# ForceReset.net
KiCad netlist of a schematic drawn in EAGLE
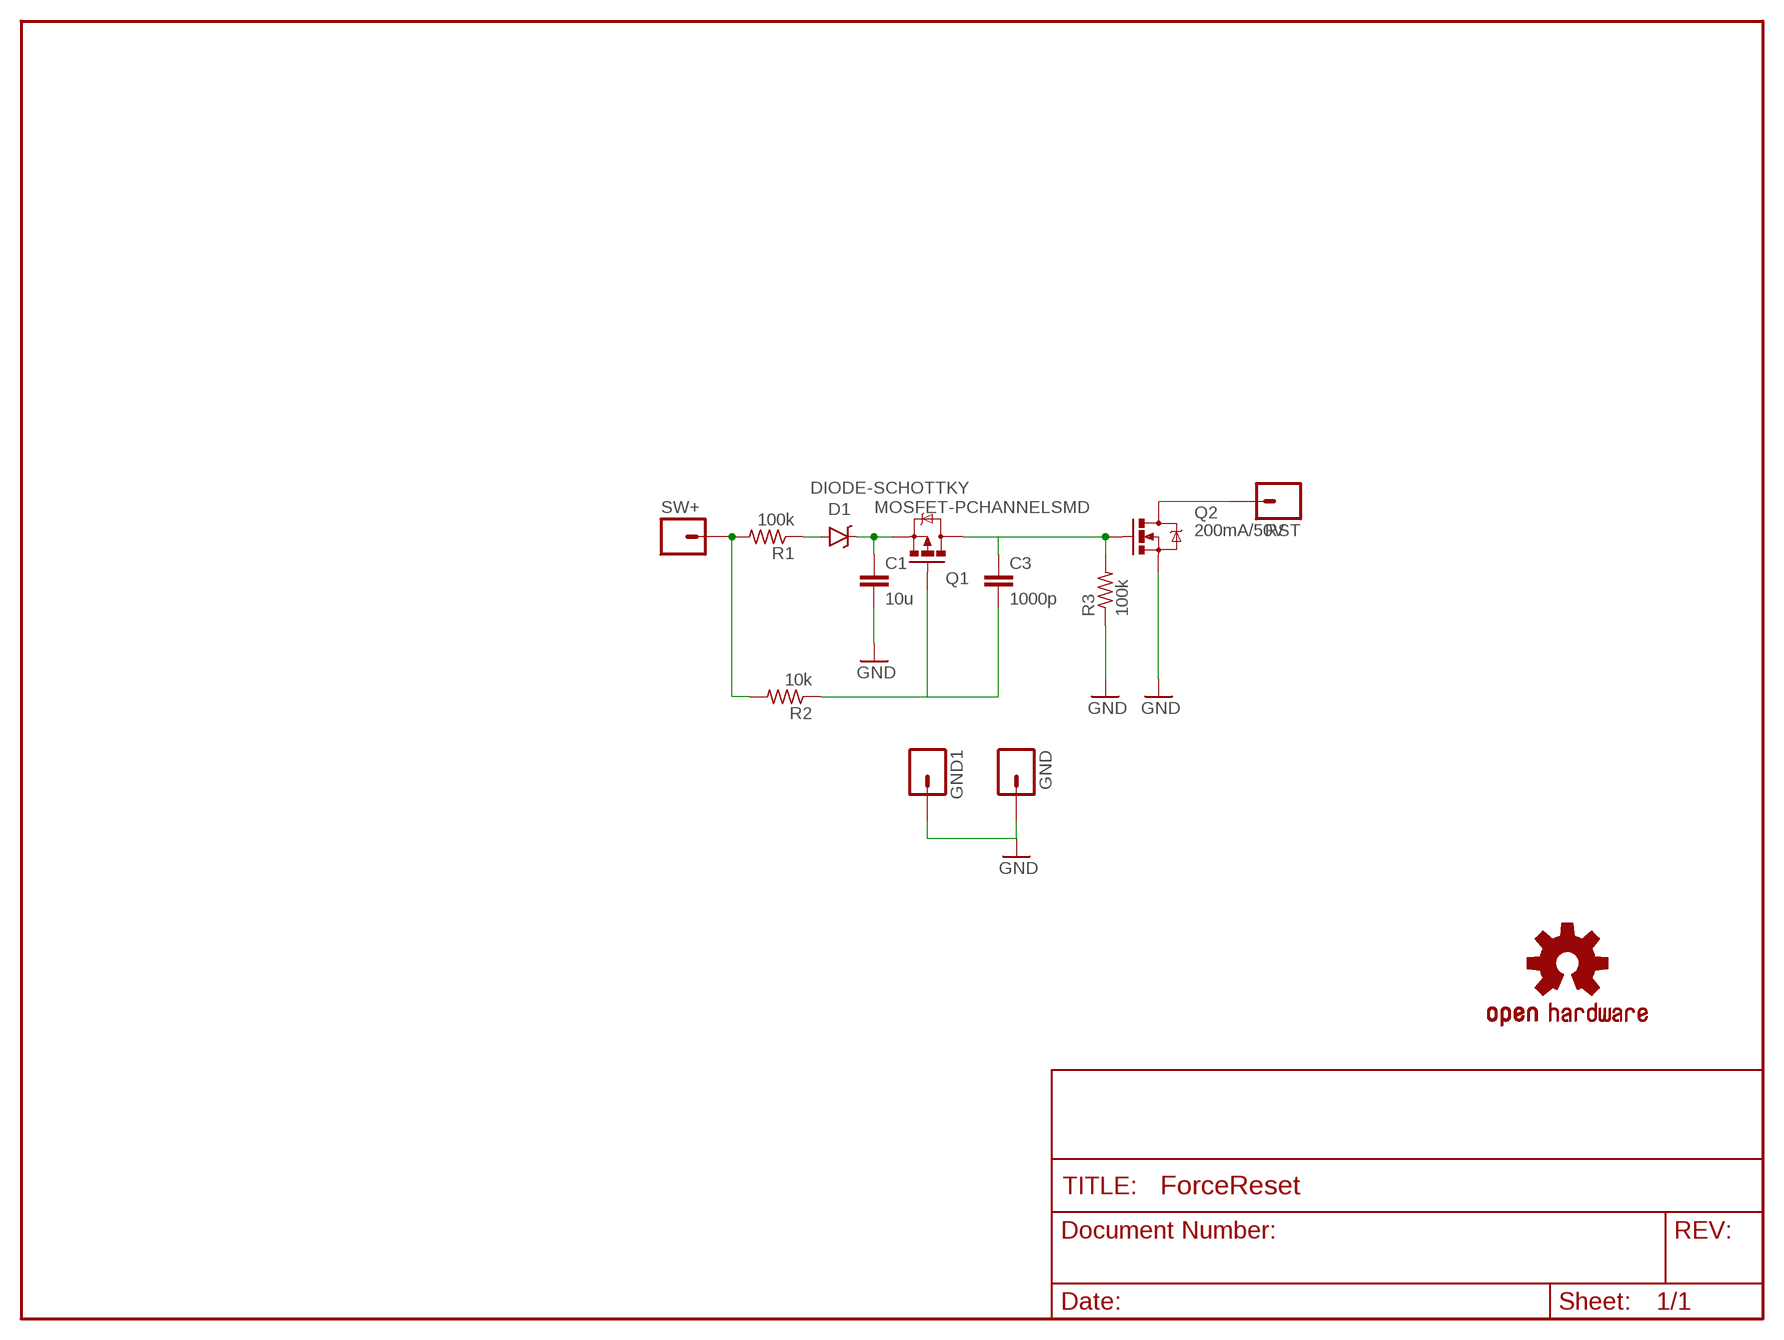
[diagram p0: schematic, sheet 1]

(export (version "E")
  (design (tool "Eeschema 10.0.6"))
  (components
    (comp (ref "C1")
      (value "10u")
      (footprint "eagle-import:1608")
      (libsource (lib "eagle-import") (part "CAP1608"))
    )
    (comp (ref "C3")
      (value "1000p")
      (footprint "eagle-import:1608")
      (libsource (lib "eagle-import") (part "CAP1608"))
    )
    (comp (ref "D1")
      (value "DIODE-SCHOTTKY")
      (footprint "eagle-import:TUMD2")
      (libsource (lib "eagle-import") (part "DIODE-SCHOTTKY"))
    )
    (comp (ref "GND")
      (value "M01PTH")
      (footprint "eagle-import:1X01")
      (libsource (lib "eagle-import") (part "M01PTH"))
    )
    (comp (ref "GND1")
      (value "M01PTH")
      (footprint "eagle-import:1X01")
      (libsource (lib "eagle-import") (part "M01PTH"))
    )
    (comp (ref "LOGO1")
      (value "OSHW-LOGOS")
      (footprint "eagle-import:OSHW-LOGO-S")
      (libsource (lib "eagle-import") (part "OSHW-LOGOS"))
    )
    (comp (ref "Q1")
      (value "MOSFET-PCHANNELSMD")
      (footprint "eagle-import:SOT23-3")
      (libsource (lib "eagle-import") (part "MOSFET-PCHANNELSMD"))
    )
    (comp (ref "Q2")
      (value "200mA/50V")
      (footprint "eagle-import:SOT23-3")
      (libsource (lib "eagle-import") (part "MOSFET-NCHANNELBSS138"))
    )
    (comp (ref "R1")
      (value "100k")
      (footprint "eagle-import:1608")
      (libsource (lib "eagle-import") (part "R-US_1608"))
    )
    (comp (ref "R2")
      (value "10k")
      (footprint "eagle-import:1608")
      (libsource (lib "eagle-import") (part "R-US_1608"))
    )
    (comp (ref "R3")
      (value "100k")
      (footprint "eagle-import:1608")
      (libsource (lib "eagle-import") (part "R-US_1608"))
    )
    (comp (ref "RST")
      (value "M01PTH")
      (footprint "eagle-import:1X01")
      (libsource (lib "eagle-import") (part "M01PTH"))
    )
    (comp (ref "SW+")
      (value "M01PTH")
      (footprint "eagle-import:1X01")
      (libsource (lib "eagle-import") (part "M01PTH"))
    )
  )
  (nets
    (net (code "1") (name "GND") (class "Default")
      (node (ref "C1") (pin "P$2") (pinfunction "2_P$2") (pintype "passive"))
      (node (ref "GND") (pin "1") (pinfunction "1_1") (pintype "passive"))
      (node (ref "GND1") (pin "1") (pinfunction "1_1") (pintype "passive"))
      (node (ref "Q2") (pin "2") (pinfunction "S_2") (pintype "passive"))
      (node (ref "R3") (pin "P$1") (pinfunction "1_P$1") (pintype "passive"))
    )
    (net (code "2") (name "Net-(C1-1)") (class "Default")
      (node (ref "C1") (pin "P$1") (pinfunction "1_P$1") (pintype "passive"))
      (node (ref "D1") (pin "C") (pinfunction "C_C") (pintype "passive"))
      (node (ref "Q1") (pin "2") (pinfunction "S_2") (pintype "passive"))
    )
    (net (code "3") (name "Net-(C3-1)") (class "Default")
      (node (ref "C3") (pin "P$1") (pinfunction "1_P$1") (pintype "passive"))
      (node (ref "Q1") (pin "3") (pinfunction "D_3") (pintype "passive"))
      (node (ref "Q2") (pin "1") (pinfunction "G_1") (pintype "passive"))
      (node (ref "R3") (pin "P$2") (pinfunction "2_P$2") (pintype "passive"))
    )
    (net (code "4") (name "Net-(C3-2)") (class "Default")
      (node (ref "C3") (pin "P$2") (pinfunction "2_P$2") (pintype "passive"))
      (node (ref "Q1") (pin "1") (pinfunction "G_1") (pintype "passive"))
      (node (ref "R2") (pin "P$1") (pinfunction "1_P$1") (pintype "passive"))
    )
    (net (code "5") (name "Net-(Q2-D)") (class "Default")
      (node (ref "Q2") (pin "3") (pinfunction "D_3") (pintype "passive"))
      (node (ref "RST") (pin "1") (pinfunction "1_1") (pintype "passive"))
    )
    (net (code "6") (name "Net-(R1-1)") (class "Default")
      (node (ref "D1") (pin "A") (pinfunction "A_A") (pintype "passive"))
      (node (ref "R1") (pin "P$1") (pinfunction "1_P$1") (pintype "passive"))
    )
    (net (code "7") (name "Net-(R1-2)") (class "Default")
      (node (ref "R1") (pin "P$2") (pinfunction "2_P$2") (pintype "passive"))
      (node (ref "R2") (pin "P$2") (pinfunction "2_P$2") (pintype "passive"))
      (node (ref "SW+") (pin "1") (pinfunction "1_1") (pintype "passive"))
    )
  )
)
